# glass-suction.net
KiCad netlist of a schematic drawn in EasyEDA
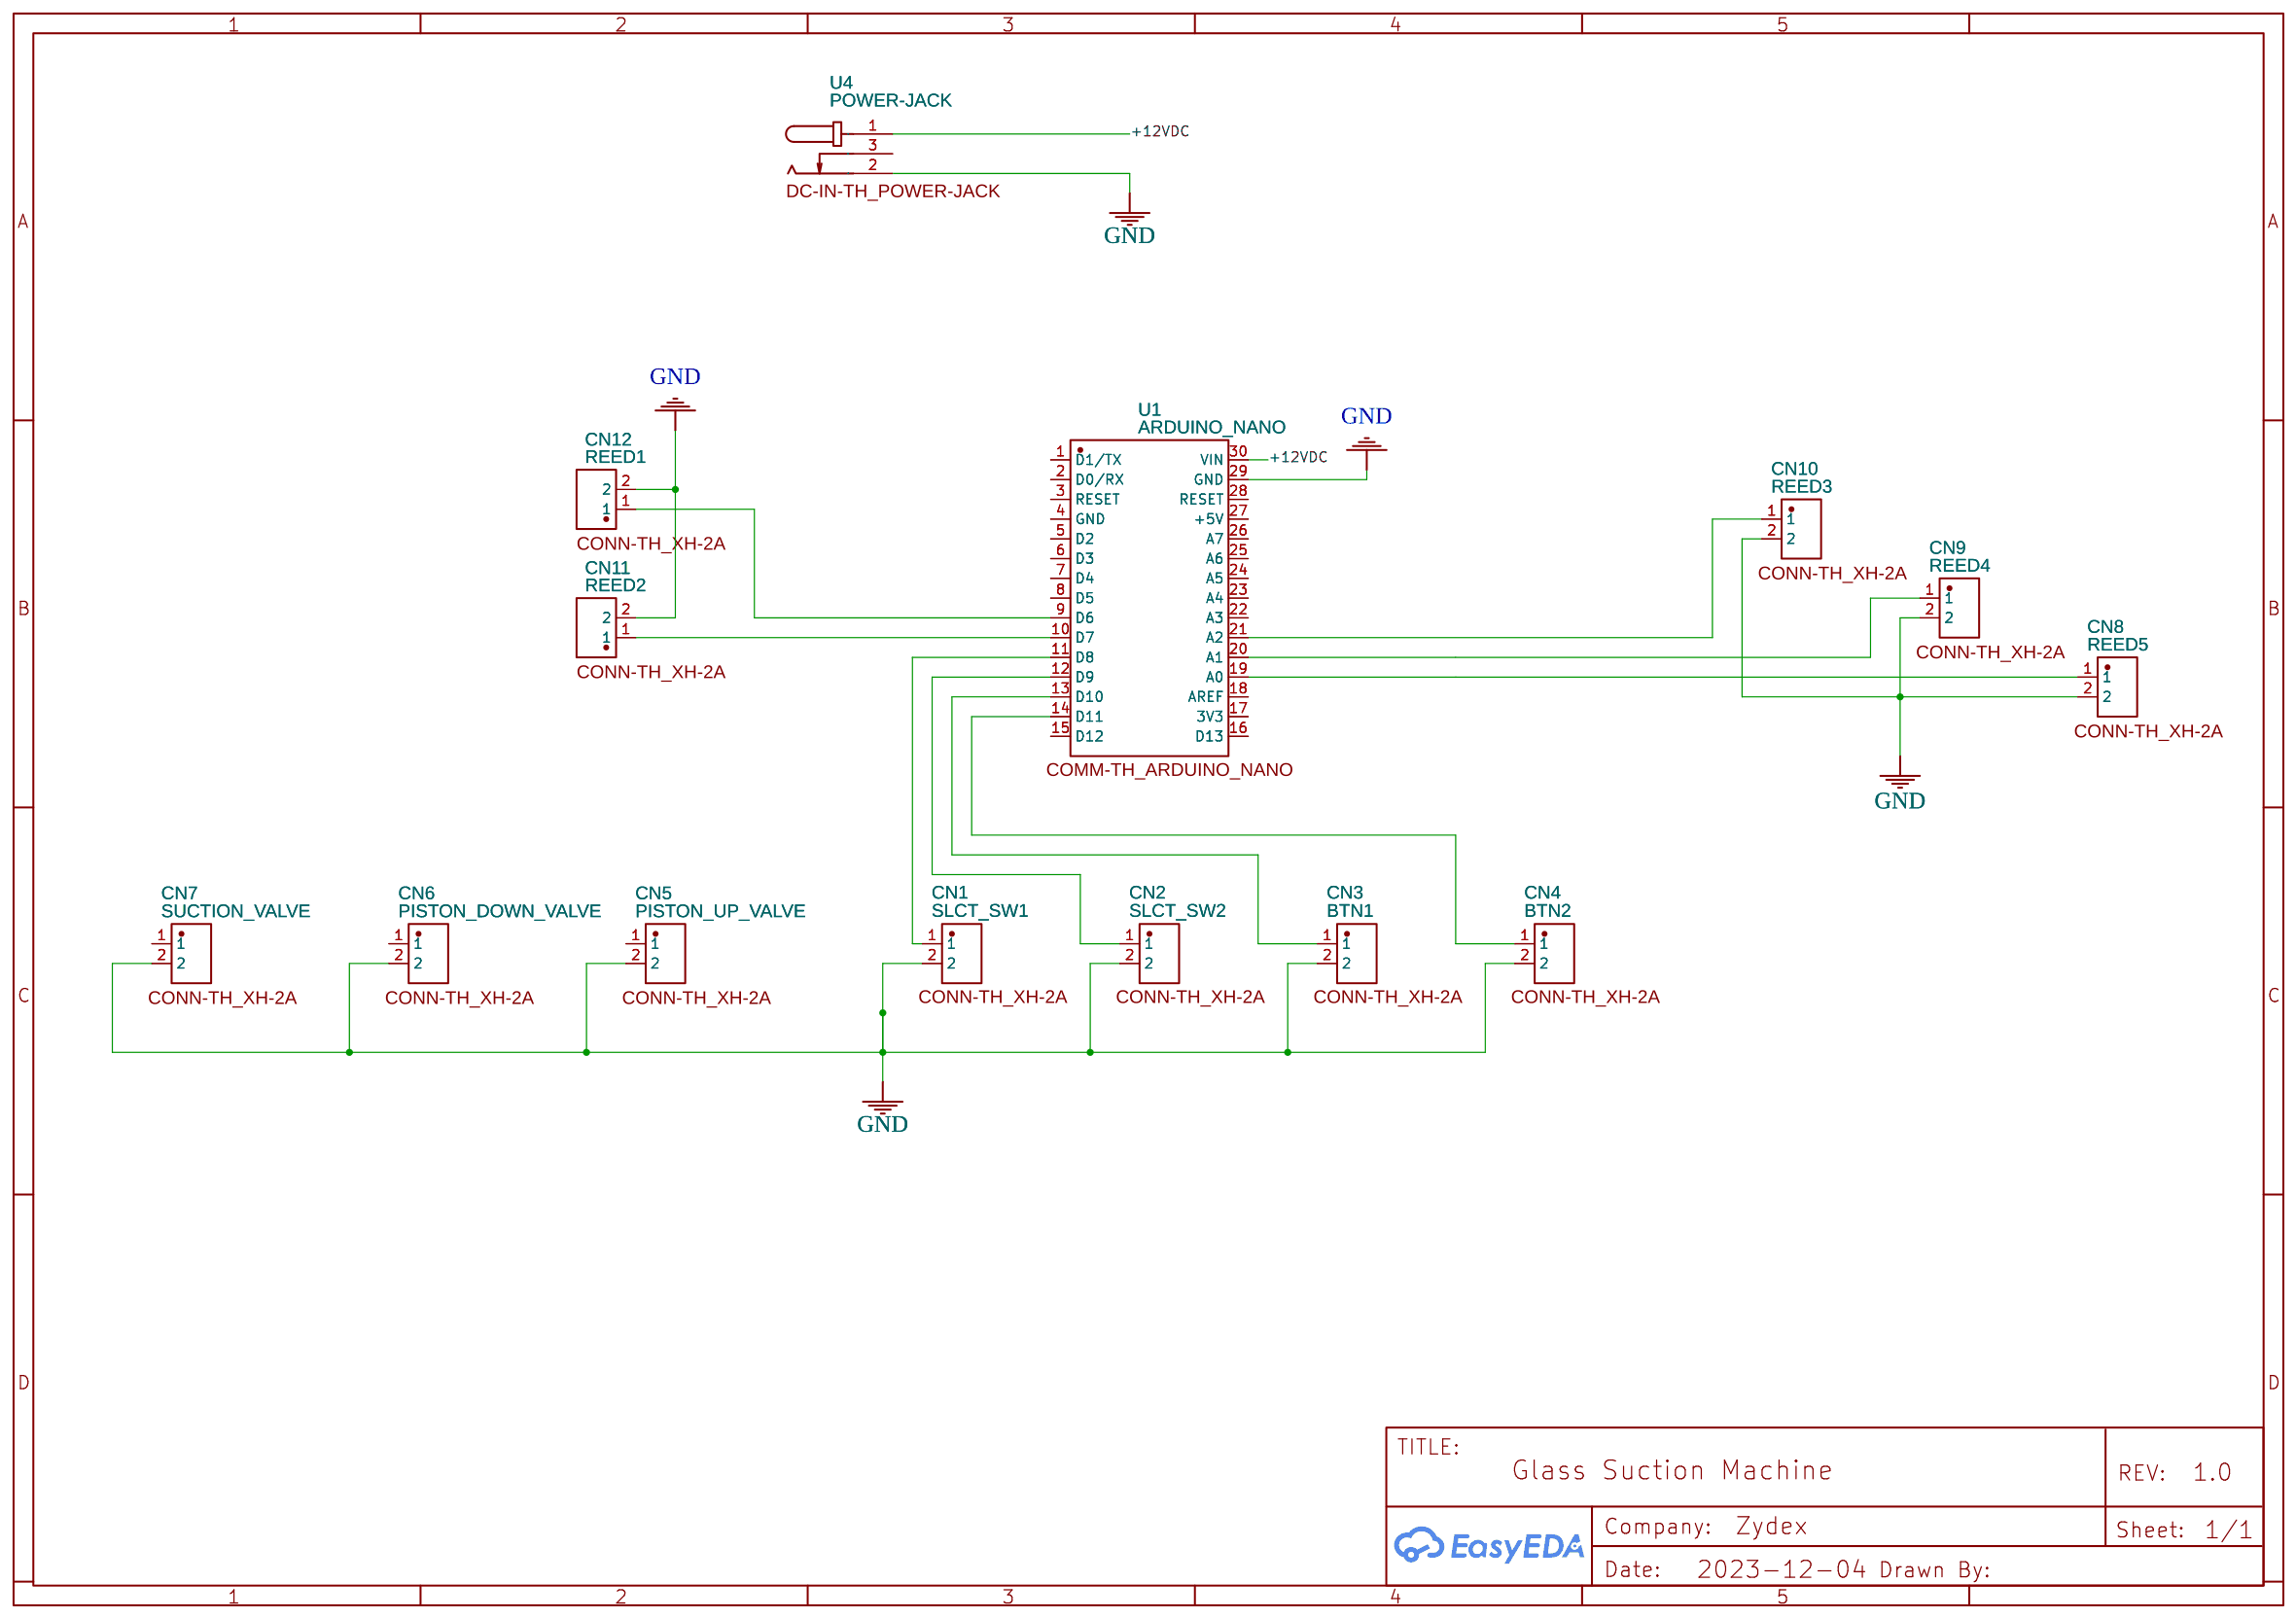
[diagram p0: schematic sheet]

(export (version "E")
  (design (tool "Eeschema 10.0.6"))
  (components
    (comp (ref "CN1")
      (value "SLCT_SW1")
      (fields (field (name "Manufacturer Part") "XH2.54-2A"))
      (libsource (lib "") (part "XH2.54-2A_1"))
    )
    (comp (ref "CN2")
      (value "SLCT_SW2")
      (fields (field (name "Manufacturer Part") "XH2.54-2A"))
      (libsource (lib "") (part "XH2.54-2A_1"))
    )
    (comp (ref "CN3")
      (value "BTN1")
      (fields (field (name "Manufacturer Part") "XH2.54-2A"))
      (libsource (lib "") (part "XH2.54-2A_1"))
    )
    (comp (ref "CN4")
      (value "BTN2")
      (fields (field (name "Manufacturer Part") "XH2.54-2A"))
      (libsource (lib "") (part "XH2.54-2A_1"))
    )
    (comp (ref "CN5")
      (value "PISTON_UP_VALVE")
      (fields (field (name "Manufacturer Part") "XH2.54-2A"))
      (libsource (lib "") (part "XH2.54-2A"))
    )
    (comp (ref "CN6")
      (value "PISTON_DOWN_VALVE")
      (fields (field (name "Manufacturer Part") "XH2.54-2A"))
      (libsource (lib "") (part "XH2.54-2A"))
    )
    (comp (ref "CN7")
      (value "SUCTION_VALVE")
      (fields (field (name "Manufacturer Part") "XH2.54-2A"))
      (libsource (lib "") (part "XH2.54-2A"))
    )
    (comp (ref "CN8")
      (value "REED5")
      (fields (field (name "Manufacturer Part") "XH2.54-2A"))
      (libsource (lib "") (part "XH2.54-2A"))
    )
    (comp (ref "CN9")
      (value "REED4")
      (fields (field (name "Manufacturer Part") "XH2.54-2A"))
      (libsource (lib "") (part "XH2.54-2A"))
    )
    (comp (ref "CN10")
      (value "REED3")
      (fields (field (name "Manufacturer Part") "XH2.54-2A"))
      (libsource (lib "") (part "XH2.54-2A"))
    )
    (comp (ref "CN11")
      (value "REED2")
      (fields (field (name "Manufacturer Part") "XH2.54-2A"))
      (libsource (lib "") (part "XH2.54-2A_2"))
    )
    (comp (ref "CN12")
      (value "REED1")
      (fields (field (name "Manufacturer Part") "XH2.54-2A"))
      (libsource (lib "") (part "XH2.54-2A_2"))
    )
    (comp (ref "U1") (value "ARDUINO_NANO") (libsource (lib "") (part "ARDUINO_NANO")))
    (comp (ref "U4")
      (value "POWER-JACK")
      (fields (field (name "Manufacturer") "索峰"))
      (libsource (lib "") (part "POWER-JACK"))
    )
  )
  (nets
    (net (code "1") (name "/+12VDC") (class "Default")
      (node (ref "U1") (pin "30") (pinfunction "VIN_30") (pintype "unspecified"))
      (node (ref "U4") (pin "1") (pinfunction "1_1") (pintype "unspecified"))
    )
    (net (code "2") (name "GND") (class "Default")
      (node (ref "CN1") (pin "2") (pinfunction "2_2") (pintype "unspecified"))
      (node (ref "CN10") (pin "2") (pinfunction "2_2") (pintype "unspecified"))
      (node (ref "CN11") (pin "2") (pinfunction "2_2") (pintype "unspecified"))
      (node (ref "CN12") (pin "2") (pinfunction "2_2") (pintype "unspecified"))
      (node (ref "CN2") (pin "2") (pinfunction "2_2") (pintype "unspecified"))
      (node (ref "CN3") (pin "2") (pinfunction "2_2") (pintype "unspecified"))
      (node (ref "CN4") (pin "2") (pinfunction "2_2") (pintype "unspecified"))
      (node (ref "CN5") (pin "2") (pinfunction "2_2") (pintype "unspecified"))
      (node (ref "CN6") (pin "2") (pinfunction "2_2") (pintype "unspecified"))
      (node (ref "CN7") (pin "2") (pinfunction "2_2") (pintype "unspecified"))
      (node (ref "CN8") (pin "2") (pinfunction "2_2") (pintype "unspecified"))
      (node (ref "CN9") (pin "2") (pinfunction "2_2") (pintype "unspecified"))
      (node (ref "U1") (pin "29") (pinfunction "GND_29") (pintype "unspecified"))
      (node (ref "U4") (pin "2") (pinfunction "2_2") (pintype "unspecified"))
    )
    (net (code "3") (name "Net-(U1-A0)") (class "Default")
      (node (ref "CN8") (pin "1") (pinfunction "1_1") (pintype "unspecified"))
      (node (ref "U1") (pin "19") (pinfunction "A0_19") (pintype "unspecified"))
    )
    (net (code "4") (name "Net-(U1-A1)") (class "Default")
      (node (ref "CN9") (pin "1") (pinfunction "1_1") (pintype "unspecified"))
      (node (ref "U1") (pin "20") (pinfunction "A1_20") (pintype "unspecified"))
    )
    (net (code "5") (name "Net-(U1-A2)") (class "Default")
      (node (ref "CN10") (pin "1") (pinfunction "1_1") (pintype "unspecified"))
      (node (ref "U1") (pin "21") (pinfunction "A2_21") (pintype "unspecified"))
    )
    (net (code "6") (name "Net-(U1-D6)") (class "Default")
      (node (ref "CN12") (pin "1") (pinfunction "1_1") (pintype "unspecified"))
      (node (ref "U1") (pin "9") (pinfunction "D6_9") (pintype "unspecified"))
    )
    (net (code "7") (name "Net-(U1-D7)") (class "Default")
      (node (ref "CN11") (pin "1") (pinfunction "1_1") (pintype "unspecified"))
      (node (ref "U1") (pin "10") (pinfunction "D7_10") (pintype "unspecified"))
    )
    (net (code "8") (name "Net-(U1-D8)") (class "Default")
      (node (ref "CN1") (pin "1") (pinfunction "1_1") (pintype "unspecified"))
      (node (ref "U1") (pin "11") (pinfunction "D8_11") (pintype "unspecified"))
    )
    (net (code "9") (name "Net-(U1-D9)") (class "Default")
      (node (ref "CN2") (pin "1") (pinfunction "1_1") (pintype "unspecified"))
      (node (ref "U1") (pin "12") (pinfunction "D9_12") (pintype "unspecified"))
    )
    (net (code "10") (name "Net-(U1-D10)") (class "Default")
      (node (ref "CN3") (pin "1") (pinfunction "1_1") (pintype "unspecified"))
      (node (ref "U1") (pin "13") (pinfunction "D10_13") (pintype "unspecified"))
    )
    (net (code "11") (name "Net-(U1-D11)") (class "Default")
      (node (ref "CN4") (pin "1") (pinfunction "1_1") (pintype "unspecified"))
      (node (ref "U1") (pin "14") (pinfunction "D11_14") (pintype "unspecified"))
    )
    (net (code "12") (name "unconnected-(CN5-Pad1)") (class "Default")
      (node (ref "CN5") (pin "1") (pinfunction "1_1") (pintype "unspecified"))
    )
    (net (code "13") (name "unconnected-(CN6-Pad1)") (class "Default")
      (node (ref "CN6") (pin "1") (pinfunction "1_1") (pintype "unspecified"))
    )
    (net (code "14") (name "unconnected-(CN7-Pad1)") (class "Default")
      (node (ref "CN7") (pin "1") (pinfunction "1_1") (pintype "unspecified"))
    )
    (net (code "15") (name "unconnected-(U1-+5V-Pad27)") (class "Default")
      (node (ref "U1") (pin "27") (pinfunction "+5V_27") (pintype "unspecified"))
    )
    (net (code "16") (name "unconnected-(U1-3V3-Pad17)") (class "Default")
      (node (ref "U1") (pin "17") (pinfunction "3V3_17") (pintype "unspecified"))
    )
    (net (code "17") (name "unconnected-(U1-A3-Pad22)") (class "Default")
      (node (ref "U1") (pin "22") (pinfunction "A3_22") (pintype "unspecified"))
    )
    (net (code "18") (name "unconnected-(U1-A4-Pad23)") (class "Default")
      (node (ref "U1") (pin "23") (pinfunction "A4_23") (pintype "unspecified"))
    )
    (net (code "19") (name "unconnected-(U1-A5-Pad24)") (class "Default")
      (node (ref "U1") (pin "24") (pinfunction "A5_24") (pintype "unspecified"))
    )
    (net (code "20") (name "unconnected-(U1-A6-Pad25)") (class "Default")
      (node (ref "U1") (pin "25") (pinfunction "A6_25") (pintype "unspecified"))
    )
    (net (code "21") (name "unconnected-(U1-A7-Pad26)") (class "Default")
      (node (ref "U1") (pin "26") (pinfunction "A7_26") (pintype "unspecified"))
    )
    (net (code "22") (name "unconnected-(U1-AREF-Pad18)") (class "Default")
      (node (ref "U1") (pin "18") (pinfunction "AREF_18") (pintype "unspecified"))
    )
    (net (code "23") (name "unconnected-(U1-D0{slash}RX-Pad2)") (class "Default")
      (node (ref "U1") (pin "2") (pinfunction "D0/RX_2") (pintype "unspecified"))
    )
    (net (code "24") (name "unconnected-(U1-D1{slash}TX-Pad1)") (class "Default")
      (node (ref "U1") (pin "1") (pinfunction "D1/TX_1") (pintype "unspecified"))
    )
    (net (code "25") (name "unconnected-(U1-D2-Pad5)") (class "Default")
      (node (ref "U1") (pin "5") (pinfunction "D2_5") (pintype "unspecified"))
    )
    (net (code "26") (name "unconnected-(U1-D3-Pad6)") (class "Default")
      (node (ref "U1") (pin "6") (pinfunction "D3_6") (pintype "unspecified"))
    )
    (net (code "27") (name "unconnected-(U1-D4-Pad7)") (class "Default")
      (node (ref "U1") (pin "7") (pinfunction "D4_7") (pintype "unspecified"))
    )
    (net (code "28") (name "unconnected-(U1-D5-Pad8)") (class "Default")
      (node (ref "U1") (pin "8") (pinfunction "D5_8") (pintype "unspecified"))
    )
    (net (code "29") (name "unconnected-(U1-D12-Pad15)") (class "Default")
      (node (ref "U1") (pin "15") (pinfunction "D12_15") (pintype "unspecified"))
    )
    (net (code "30") (name "unconnected-(U1-D13-Pad16)") (class "Default")
      (node (ref "U1") (pin "16") (pinfunction "D13_16") (pintype "unspecified"))
    )
    (net (code "31") (name "unconnected-(U1-GND-Pad4)") (class "Default")
      (node (ref "U1") (pin "4") (pinfunction "GND_4") (pintype "unspecified"))
    )
    (net (code "32") (name "unconnected-(U1-RESET-Pad3)") (class "Default")
      (node (ref "U1") (pin "3") (pinfunction "RESET_3") (pintype "unspecified"))
    )
    (net (code "33") (name "unconnected-(U1-RESET-Pad28)") (class "Default")
      (node (ref "U1") (pin "28") (pinfunction "RESET_28") (pintype "unspecified"))
    )
    (net (code "34") (name "unconnected-(U4-Pad3)") (class "Default")
      (node (ref "U4") (pin "3") (pinfunction "3_3") (pintype "unspecified"))
    )
  )
)
